# measurment_iq.net
KiCad netlist of a schematic drawn in Altium Designer
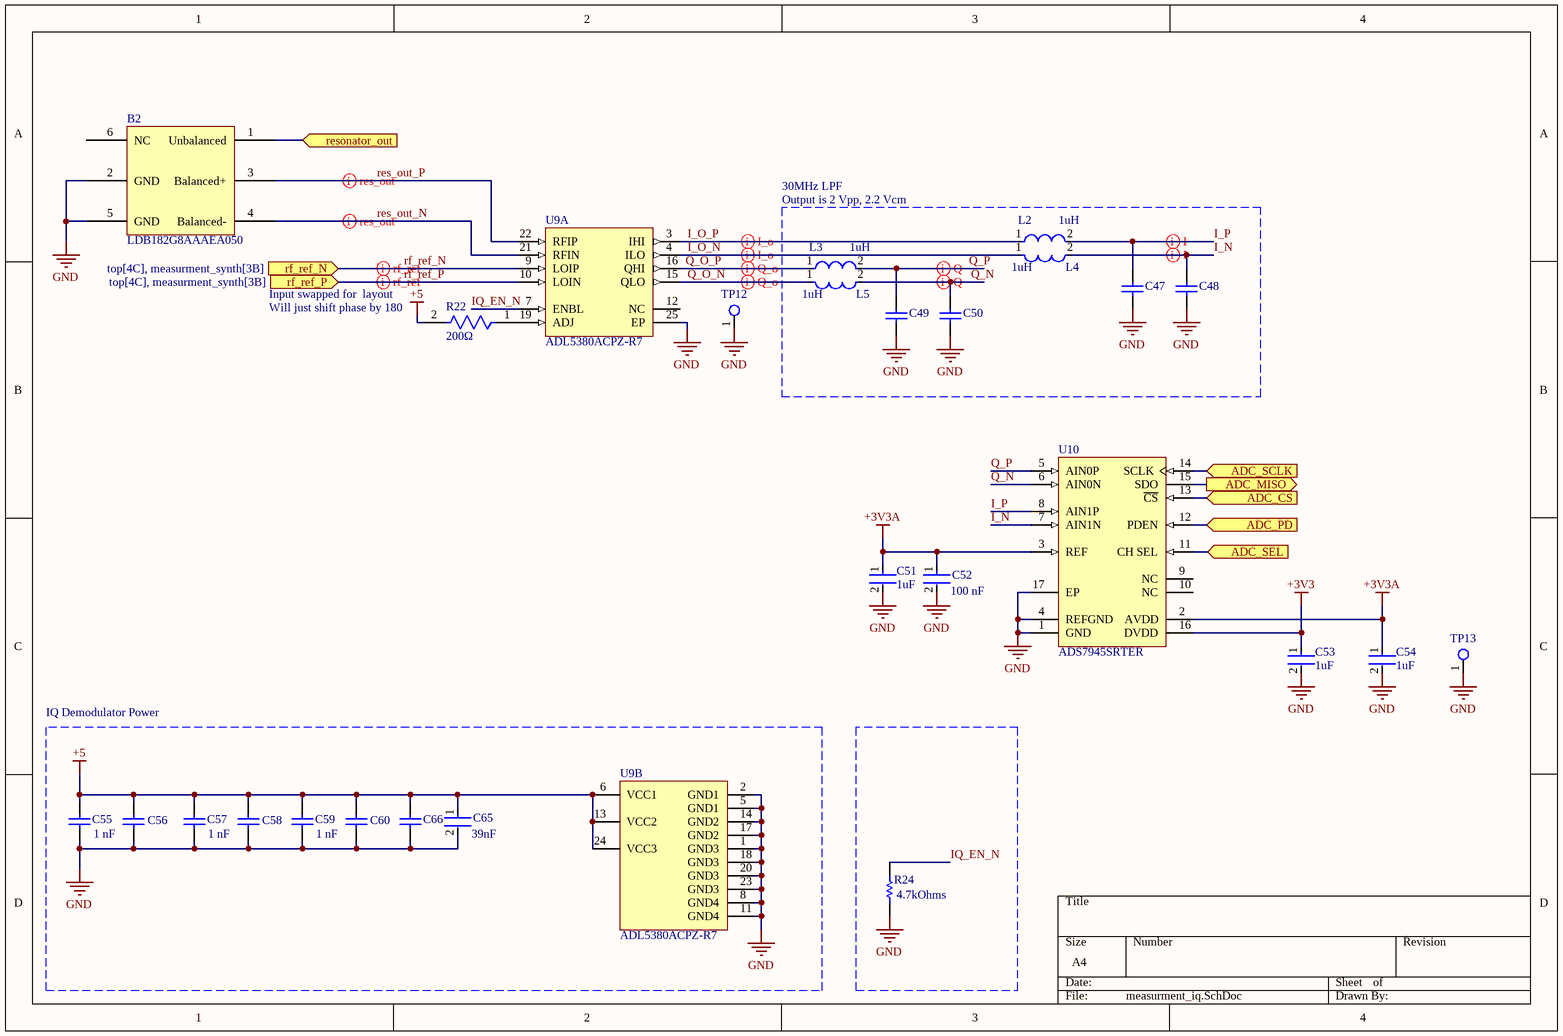
[diagram p0: measurment_iq.SchDoc]

(export (version "E")
  (design (tool "Eeschema 10.0.6"))
  (components
    (comp (ref "B2")
      (value "LDB182G8AAAEA050")
      (footprint "Balum")
      (libsource (lib "fydp") (part "LDB182G8AAAEA050"))
    )
    (comp (ref "C47")
      (value "GRM1555C1H270JA01D")
      (footprint "CAPC1005X55X25LL05T10")
      (fields (field (name "MANUFACTURER") "Murata"))
      (libsource (lib "Altium Content Vault") (part "CAP"))
    )
    (comp (ref "C48")
      (value "GRM1555C1H270JA01D")
      (footprint "CAPC1005X55X25LL05T10")
      (fields (field (name "MANUFACTURER") "Murata"))
      (libsource (lib "Altium Content Vault") (part "CAP"))
    )
    (comp (ref "C49")
      (value "GRM1555C1H270JA01D")
      (footprint "CAPC1005X55X25LL05T10")
      (fields (field (name "MANUFACTURER") "Murata"))
      (libsource (lib "Altium Content Vault") (part "CAP"))
    )
    (comp (ref "C50")
      (value "GRM1555C1H270JA01D")
      (footprint "CAPC1005X55X25LL05T10")
      (fields (field (name "MANUFACTURER") "Murata"))
      (libsource (lib "Altium Content Vault") (part "CAP"))
    )
    (comp (ref "C51")
      (value "CL10B105KP8NNNC")
      (footprint "FP-CL10-IPC_C")
      (description "Cap Ceramic 1uF 10V X7R ±10% Pad SMD 0603 +125°C T/R")
      (fields (field (name "CAPACITANCE") "1uF") (field (name "TOLERANCE") "10%"))
      (libsource (lib "Altium Content Vault") (part "b4654b650e69147ec39a6b967a45e02"))
    )
    (comp (ref "C52")
      (value "CC0603KRX7R7BB104")
      (footprint "FP-CC0603-DA-MFG")
      (description "CAP CER 0.1UF 16V X7R 0603")
      (fields
        (field (name "OCTOPART") "https://octopart.com/cc0603krx7r7bb104-yageo-192941")
        (field (name "TOLERANCE") "0.1")
        (field (name "CAPACITANCE") "100 nF")
      )
      (libsource (lib "Altium Content Vault") (part "11868f565c42a9108669ba33697ecf6"))
    )
    (comp (ref "C53")
      (value "CL10B105KP8NNNC")
      (footprint "FP-CL10-IPC_C")
      (description "Cap Ceramic 1uF 10V X7R ±10% Pad SMD 0603 +125°C T/R")
      (fields (field (name "CAPACITANCE") "1uF") (field (name "TOLERANCE") "10%"))
      (libsource (lib "Altium Content Vault") (part "b4654b650e69147ec39a6b967a45e02"))
    )
    (comp (ref "C54")
      (value "CL10B105KP8NNNC")
      (footprint "FP-CL10-IPC_C")
      (description "Cap Ceramic 1uF 10V X7R ±10% Pad SMD 0603 +125°C T/R")
      (fields (field (name "CAPACITANCE") "1uF") (field (name "TOLERANCE") "10%"))
      (libsource (lib "Altium Content Vault") (part "b4654b650e69147ec39a6b967a45e02"))
    )
    (comp (ref "C55")
      (value "GRM155R71H102KA01D")
      (footprint "CAPC1005X55X25ML5T10")
      (description "Chip Capacitor, 1 nF, +/- 10%, 50 V, -55 to 125 degC, 0402 (1005 Metric), RoHS, Tape and Reel")
      (fields (field (name "TOLERANCE") "10%") (field (name "CAPACITANCE") "1 nF"))
      (libsource (lib "Altium Content Vault") (part "CAP-NP-2"))
    )
    (comp (ref "C56")
      (value "GRM1555C1H101JA01D")
      (footprint "CAPC1005X55X25ML05T10")
      (fields (field (name "MANUFACTURER") "Murata"))
      (libsource (lib "Altium Content Vault") (part "CAP"))
    )
    (comp (ref "C57")
      (value "GRM155R71H102KA01D")
      (footprint "CAPC1005X55X25ML5T10")
      (description "Chip Capacitor, 1 nF, +/- 10%, 50 V, -55 to 125 degC, 0402 (1005 Metric), RoHS, Tape and Reel")
      (fields (field (name "TOLERANCE") "10%") (field (name "CAPACITANCE") "1 nF"))
      (libsource (lib "Altium Content Vault") (part "CAP-NP-2"))
    )
    (comp (ref "C58")
      (value "GRM1555C1H101JA01D")
      (footprint "CAPC1005X55X25ML05T10")
      (fields (field (name "MANUFACTURER") "Murata"))
      (libsource (lib "Altium Content Vault") (part "CAP"))
    )
    (comp (ref "C59")
      (value "GRM155R71H102KA01D")
      (footprint "CAPC1005X55X25ML5T10")
      (description "Chip Capacitor, 1 nF, +/- 10%, 50 V, -55 to 125 degC, 0402 (1005 Metric), RoHS, Tape and Reel")
      (fields (field (name "TOLERANCE") "10%") (field (name "CAPACITANCE") "1 nF"))
      (libsource (lib "Altium Content Vault") (part "CAP-NP-2"))
    )
    (comp (ref "C60")
      (value "GRM1555C1H101JA01D")
      (footprint "CAPC1005X55X25ML05T10")
      (fields (field (name "MANUFACTURER") "Murata"))
      (libsource (lib "Altium Content Vault") (part "CAP"))
    )
    (comp (ref "C65")
      (value "GCM155R71C393KA37D")
      (footprint "FP-GCM155-0_05-IPC_B")
      (description "Ceramic Capacitor for Automotive 39nF ±10% 16VDC X7R 0402 Paper T/R")
      (fields (field (name "CAPACITANCE") "39nF") (field (name "TOLERANCE") "10%"))
      (libsource (lib "Altium Content Vault") (part "02cd4be3c70576c341d710602a673aa"))
    )
    (comp (ref "C66")
      (value "GRM1555C1H270JA01D")
      (footprint "CAPC1005X55X25LL05T10")
      (fields (field (name "MANUFACTURER") "Murata"))
      (libsource (lib "Altium Content Vault") (part "CAP"))
    )
    (comp (ref "L2")
      (value "LQM21PN1R0NGRD")
      (footprint "FP-LQM21PH_G0-IPC_C")
      (description "Multilayer Type Inductor for Power Lines, 0805 (2012), 1μH, 30%, 0.0825Ω, 1.3A")
      (fields (field (name "INDUCTANCE") "1uH") (field (name "TOLERANCE") "30%"))
      (libsource (lib "") (part "725321dda6339637d4d059423bc1c3c_1"))
    )
    (comp (ref "L3")
      (value "LQM21PN1R0NGRD")
      (footprint "FP-LQM21PH_G0-IPC_C")
      (description "Multilayer Type Inductor for Power Lines, 0805 (2012), 1μH, 30%, 0.0825Ω, 1.3A")
      (fields (field (name "INDUCTANCE") "1uH") (field (name "TOLERANCE") "30%"))
      (libsource (lib "") (part "725321dda6339637d4d059423bc1c3c_1"))
    )
    (comp (ref "L4")
      (value "LQM21PN1R0NGRD")
      (footprint "FP-LQM21PH_G0-IPC_C")
      (description "Multilayer Type Inductor for Power Lines, 0805 (2012), 1μH, 30%, 0.0825Ω, 1.3A")
      (fields (field (name "INDUCTANCE") "1uH") (field (name "TOLERANCE") "30%"))
      (libsource (lib "Altium Content Vault") (part "725321dda6339637d4d059423bc1c3c"))
    )
    (comp (ref "L5")
      (value "LQM21PN1R0NGRD")
      (footprint "FP-LQM21PH_G0-IPC_C")
      (description "Multilayer Type Inductor for Power Lines, 0805 (2012), 1μH, 30%, 0.0825Ω, 1.3A")
      (fields (field (name "INDUCTANCE") "1uH") (field (name "TOLERANCE") "30%"))
      (libsource (lib "Altium Content Vault") (part "725321dda6339637d4d059423bc1c3c"))
    )
    (comp (ref "R22")
      (value "200Ω")
      (footprint "FP-RT0402-MFG")
      (description "RES SMD 200 OHM 0.1% 1/16W 0402")
      (fields (field (name "TOLERANCE") "0.001") (field (name "MANUFACTURER PART NUMBER") "RT0402BRD07200RL"))
      (libsource (lib "Altium Content Vault") (part "1029c3af85768c4190bb7ad29bc67b5"))
    )
    (comp (ref "R24")
      (value "RC0603FR-074K7L")
      (footprint "RESC1608X55X25LL10T15")
      (description "Chip Resistor, 4.7 KOhm, +/- 1%, 0.1 W, -55 to 155 degC, 0603 (1608 Metric), RoHS, Tape and Reel")
      (fields
        (field (name "MANUFACTURER") "Yageo")
        (field (name "RESISTANCE") "4.7kOhms")
        (field (name "TOLERANCE") "1%")
      )
      (libsource (lib "Altium Content Vault") (part "RES-2"))
    )
    (comp (ref "TP12")
      (value "Test Point")
      (footprint "test_point")
      (libsource (lib "fydp") (part "Test Point"))
    )
    (comp (ref "TP13")
      (value "Test Point")
      (footprint "test_point")
      (libsource (lib "fydp") (part "Test Point"))
    )
    (comp (ref "U9")
      (value "ADL5380ACPZ-R7")
      (footprint "ADI-CP-24-3_N")
      (description "400 MHz to 6 GHz Quadrature Demodulator, CP-24-3, Pb-Free, 1500 Reel")
      (libsource (lib "Altium Content Vault") (part "ADI-ADL5380-CP-24-3"))
    )
    (comp (ref "U10")
      (value "ADS7945SRTER")
      (footprint "TI-RTE16-1700X1700TP_V")
      (fields (field (name "MANUFACTURER") "Texas Instruments"))
      (libsource (lib "Altium Content Vault") (part "TI-ADS794XRTE16-1700X1700TP"))
    )
  )
  (nets
    (net (code "1") (name "+3V3") (class "Default")
      (node (ref "C53") (pin "1") (pinfunction "1_1") (pintype "passive"))
      (node (ref "U10") (pin "16") (pinfunction "DVDD_16") (pintype "power_in"))
    )
    (net (code "2") (name "+3V3A") (class "Default")
      (node (ref "C51") (pin "1") (pinfunction "1_1") (pintype "passive"))
      (node (ref "C52") (pin "1") (pinfunction "1_1") (pintype "passive"))
      (node (ref "C54") (pin "1") (pinfunction "1_1") (pintype "passive"))
      (node (ref "U10") (pin "2") (pinfunction "AVDD_2") (pintype "power_in"))
      (node (ref "U10") (pin "3") (pinfunction "REF_3") (pintype "input"))
    )
    (net (code "3") (name "+5") (class "Default")
      (node (ref "C55") (pin "2") (pinfunction "2_2") (pintype "passive"))
      (node (ref "C56") (pin "2") (pinfunction "2_2") (pintype "passive"))
      (node (ref "C57") (pin "2") (pinfunction "2_2") (pintype "passive"))
      (node (ref "C58") (pin "2") (pinfunction "2_2") (pintype "passive"))
      (node (ref "C59") (pin "2") (pinfunction "2_2") (pintype "passive"))
      (node (ref "C60") (pin "2") (pinfunction "2_2") (pintype "passive"))
      (node (ref "C65") (pin "1") (pinfunction "1_1") (pintype "passive"))
      (node (ref "C66") (pin "2") (pinfunction "2_2") (pintype "passive"))
      (node (ref "R22") (pin "2") (pinfunction "2_2") (pintype "passive"))
      (node (ref "U9") (pin "13") (pinfunction "VCC2_13") (pintype "power_in"))
      (node (ref "U9") (pin "24") (pinfunction "VCC3_24") (pintype "power_in"))
      (node (ref "U9") (pin "6") (pinfunction "VCC1_6") (pintype "power_in"))
    )
    (net (code "4") (name "/ADC_CS") (class "Default")
      (node (ref "U10") (pin "13") (pinfunction "~{CS}_13") (pintype "input"))
    )
    (net (code "5") (name "/ADC_MISO") (class "Default")
      (node (ref "U10") (pin "15") (pinfunction "SDO_15") (pintype "tri_state"))
    )
    (net (code "6") (name "/ADC_PD") (class "Default")
      (node (ref "U10") (pin "12") (pinfunction "PDEN_12") (pintype "input"))
    )
    (net (code "7") (name "/ADC_SCLK") (class "Default")
      (node (ref "U10") (pin "14") (pinfunction "SCLK_14") (pintype "input"))
    )
    (net (code "8") (name "/ADC_SEL") (class "Default")
      (node (ref "U10") (pin "11") (pinfunction "CH_SEL_11") (pintype "input"))
    )
    (net (code "9") (name "/IQ_EN_N") (class "Default")
      (node (ref "R24") (pin "2") (pinfunction "2_2") (pintype "passive"))
      (node (ref "U9") (pin "7") (pinfunction "ENBL_7") (pintype "input"))
    )
    (net (code "10") (name "/I_N") (class "Default")
      (node (ref "C48") (pin "2") (pinfunction "2_2") (pintype "passive"))
      (node (ref "L4") (pin "2") (pinfunction "2_2") (pintype "passive"))
      (node (ref "U10") (pin "7") (pinfunction "AIN1N_7") (pintype "input"))
    )
    (net (code "11") (name "/I_O_N") (class "Default")
      (node (ref "L4") (pin "1") (pinfunction "1_1") (pintype "passive"))
      (node (ref "U9") (pin "4") (pinfunction "ILO_4") (pintype "output"))
    )
    (net (code "12") (name "/I_O_P") (class "Default")
      (node (ref "L2") (pin "1") (pinfunction "1_1") (pintype "passive"))
      (node (ref "U9") (pin "3") (pinfunction "IHI_3") (pintype "output"))
    )
    (net (code "13") (name "/I_P") (class "Default")
      (node (ref "C47") (pin "2") (pinfunction "2_2") (pintype "passive"))
      (node (ref "L2") (pin "2") (pinfunction "2_2") (pintype "passive"))
      (node (ref "U10") (pin "8") (pinfunction "AIN1P_8") (pintype "input"))
    )
    (net (code "14") (name "/Q_N") (class "Default")
      (node (ref "C50") (pin "2") (pinfunction "2_2") (pintype "passive"))
      (node (ref "L5") (pin "2") (pinfunction "2_2") (pintype "passive"))
      (node (ref "U10") (pin "6") (pinfunction "AIN0N_6") (pintype "input"))
    )
    (net (code "15") (name "/Q_O_N") (class "Default")
      (node (ref "L5") (pin "1") (pinfunction "1_1") (pintype "passive"))
      (node (ref "U9") (pin "15") (pinfunction "QLO_15") (pintype "output"))
    )
    (net (code "16") (name "/Q_O_P") (class "Default")
      (node (ref "L3") (pin "1") (pinfunction "1_1") (pintype "passive"))
      (node (ref "U9") (pin "16") (pinfunction "QHI_16") (pintype "output"))
    )
    (net (code "17") (name "/Q_P") (class "Default")
      (node (ref "C49") (pin "2") (pinfunction "2_2") (pintype "passive"))
      (node (ref "L3") (pin "2") (pinfunction "2_2") (pintype "passive"))
      (node (ref "U10") (pin "5") (pinfunction "AIN0P_5") (pintype "input"))
    )
    (net (code "18") (name "/res_out_N") (class "Default")
      (node (ref "B2") (pin "4") (pinfunction "Balanced-_4") (pintype "passive"))
      (node (ref "U9") (pin "21") (pinfunction "RFIN_21") (pintype "input"))
    )
    (net (code "19") (name "/res_out_P") (class "Default")
      (node (ref "B2") (pin "3") (pinfunction "Balanced+_3") (pintype "passive"))
      (node (ref "U9") (pin "22") (pinfunction "RFIP_22") (pintype "input"))
    )
    (net (code "20") (name "/resonator_out") (class "Default")
      (node (ref "B2") (pin "1") (pinfunction "Unbalanced_1") (pintype "passive"))
    )
    (net (code "21") (name "/rf_ref_N") (class "Default")
      (node (ref "U9") (pin "9") (pinfunction "LOIP_9") (pintype "input"))
    )
    (net (code "22") (name "/rf_ref_P") (class "Default")
      (node (ref "U9") (pin "10") (pinfunction "LOIN_10") (pintype "input"))
    )
    (net (code "23") (name "GND") (class "Default")
      (node (ref "B2") (pin "2") (pinfunction "GND_2") (pintype "passive"))
      (node (ref "B2") (pin "5") (pinfunction "GND_5") (pintype "passive"))
      (node (ref "C47") (pin "1") (pinfunction "1_1") (pintype "passive"))
      (node (ref "C48") (pin "1") (pinfunction "1_1") (pintype "passive"))
      (node (ref "C49") (pin "1") (pinfunction "1_1") (pintype "passive"))
      (node (ref "C50") (pin "1") (pinfunction "1_1") (pintype "passive"))
      (node (ref "C51") (pin "2") (pinfunction "2_2") (pintype "passive"))
      (node (ref "C52") (pin "2") (pinfunction "2_2") (pintype "passive"))
      (node (ref "C53") (pin "2") (pinfunction "2_2") (pintype "passive"))
      (node (ref "C54") (pin "2") (pinfunction "2_2") (pintype "passive"))
      (node (ref "C55") (pin "1") (pinfunction "1_1") (pintype "passive"))
      (node (ref "C56") (pin "1") (pinfunction "1_1") (pintype "passive"))
      (node (ref "C57") (pin "1") (pinfunction "1_1") (pintype "passive"))
      (node (ref "C58") (pin "1") (pinfunction "1_1") (pintype "passive"))
      (node (ref "C59") (pin "1") (pinfunction "1_1") (pintype "passive"))
      (node (ref "C60") (pin "1") (pinfunction "1_1") (pintype "passive"))
      (node (ref "C65") (pin "2") (pinfunction "2_2") (pintype "passive"))
      (node (ref "C66") (pin "1") (pinfunction "1_1") (pintype "passive"))
      (node (ref "R24") (pin "1") (pinfunction "1_1") (pintype "passive"))
      (node (ref "TP12") (pin "1") (pintype "passive"))
      (node (ref "TP13") (pin "1") (pintype "passive"))
      (node (ref "U10") (pin "1") (pinfunction "GND_1") (pintype "power_in"))
      (node (ref "U10") (pin "17") (pinfunction "EP_17") (pintype "passive"))
      (node (ref "U10") (pin "4") (pinfunction "REFGND_4") (pintype "power_in"))
      (node (ref "U9") (pin "1") (pinfunction "GND3_1") (pintype "power_in"))
      (node (ref "U9") (pin "11") (pinfunction "GND4_11") (pintype "power_in"))
      (node (ref "U9") (pin "14") (pinfunction "GND2_14") (pintype "power_in"))
      (node (ref "U9") (pin "17") (pinfunction "GND2_17") (pintype "power_in"))
      (node (ref "U9") (pin "18") (pinfunction "GND3_18") (pintype "power_in"))
      (node (ref "U9") (pin "2") (pinfunction "GND1_2") (pintype "power_in"))
      (node (ref "U9") (pin "20") (pinfunction "GND3_20") (pintype "power_in"))
      (node (ref "U9") (pin "23") (pinfunction "GND3_23") (pintype "power_in"))
      (node (ref "U9") (pin "25") (pinfunction "EP_25") (pintype "power_in"))
      (node (ref "U9") (pin "5") (pinfunction "GND1_5") (pintype "power_in"))
      (node (ref "U9") (pin "8") (pinfunction "GND4_8") (pintype "power_in"))
    )
    (net (code "24") (name "Net-(U9A-ADJ)") (class "Default")
      (node (ref "R22") (pin "1") (pinfunction "1_1") (pintype "passive"))
      (node (ref "U9") (pin "19") (pinfunction "ADJ_19") (pintype "input"))
    )
    (net (code "25") (name "unconnected-(B2-NC-Pad6)") (class "Default")
      (node (ref "B2") (pin "6") (pinfunction "NC_6") (pintype "passive"))
    )
    (net (code "26") (name "unconnected-(U9A-NC-Pad12)") (class "Default")
      (node (ref "U9") (pin "12") (pinfunction "NC_12") (pintype "passive"))
    )
    (net (code "27") (name "unconnected-(U10-NC-Pad9)") (class "Default")
      (node (ref "U10") (pin "9") (pinfunction "NC_9") (pintype "passive"))
    )
    (net (code "28") (name "unconnected-(U10-NC-Pad10)") (class "Default")
      (node (ref "U10") (pin "10") (pinfunction "NC_10") (pintype "passive"))
    )
  )
)
